# nixie_power.net
KiCad netlist of a schematic drawn in Altium Designer
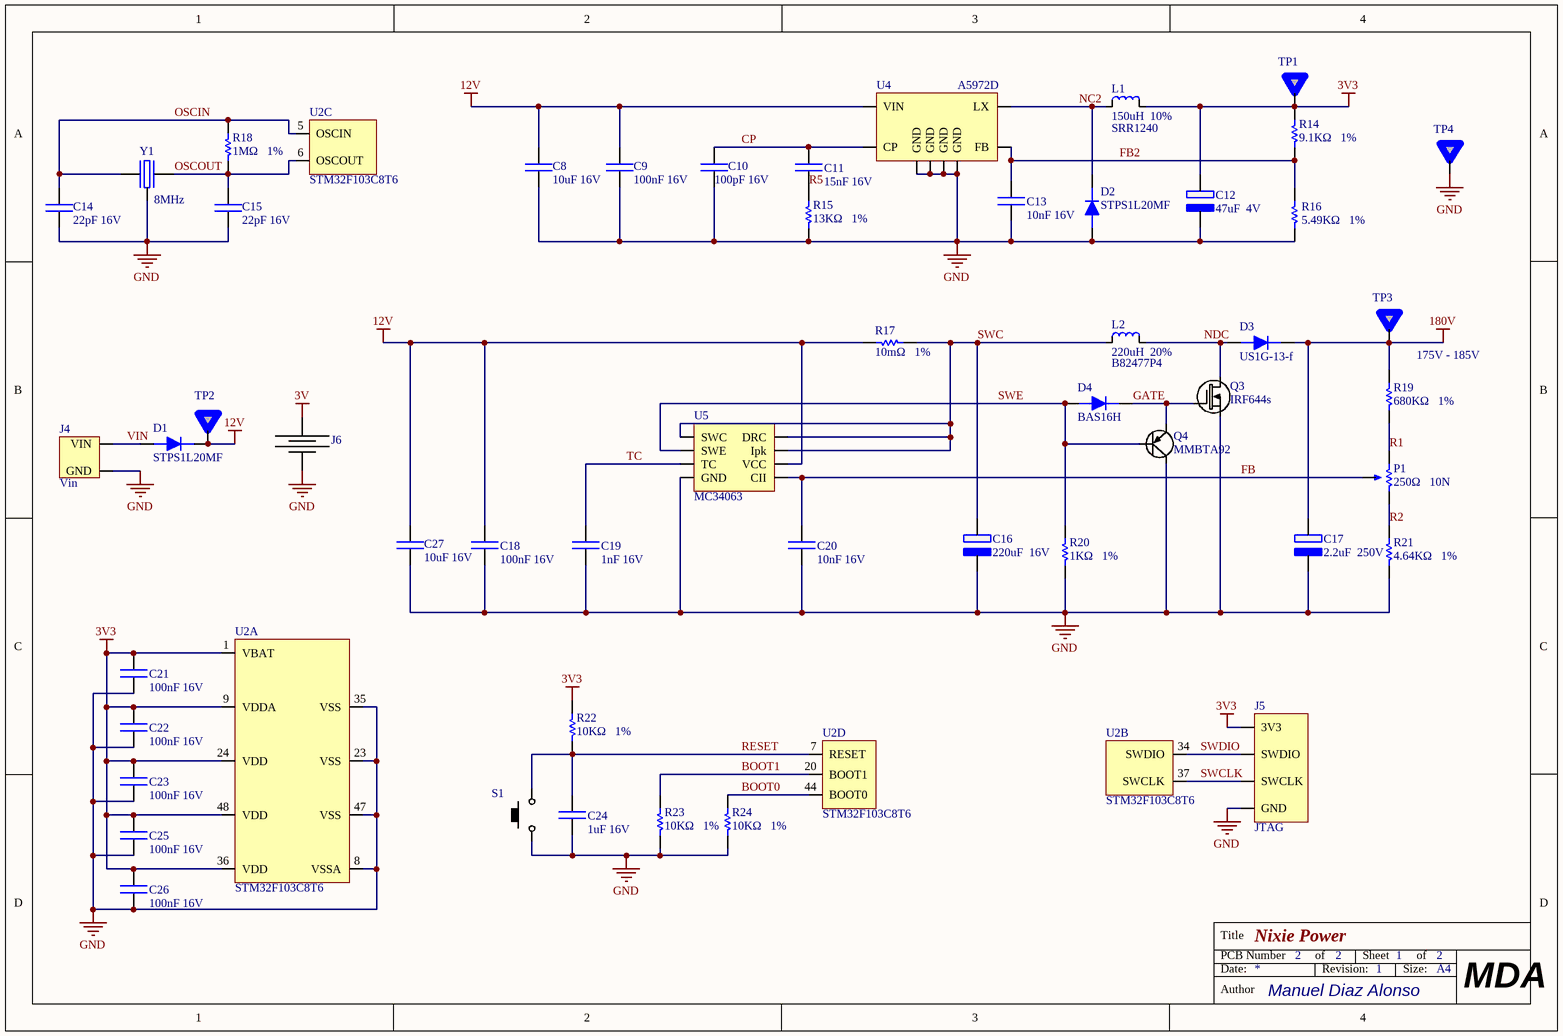
[diagram p0: nixie_power.SchDoc]

(export (version "E")
  (design (tool "Eeschema 10.0.6"))
  (components
    (comp (ref "C8") (value "10uF 16V") (footprint "0603") (libsource (lib "Nixielib") (part "CAP")))
    (comp (ref "C9") (value "100nF 16V") (footprint "0603") (libsource (lib "Nixielib") (part "CAP")))
    (comp (ref "C10") (value "100pF 16V") (footprint "0603") (libsource (lib "Nixielib") (part "CAP")))
    (comp (ref "C11") (value "15nF 16V") (footprint "0603") (libsource (lib "Nixielib") (part "CAP")))
    (comp (ref "C12")
      (value "47uF  4V")
      (footprint "AVX-B-CASE")
      (libsource (lib "Nixielib") (part "CAP_pol"))
    )
    (comp (ref "C13") (value "10nF 16V") (footprint "0603") (libsource (lib "Nixielib") (part "CAP")))
    (comp (ref "C14") (value "22pF 16V") (footprint "0603") (libsource (lib "Nixielib") (part "CAP")))
    (comp (ref "C15") (value "22pF 16V") (footprint "0603") (libsource (lib "Nixielib") (part "CAP")))
    (comp (ref "C16")
      (value "220uF  16V")
      (footprint "CAP-SIZE-F")
      (libsource (lib "Nixielib") (part "CAP_pol"))
    )
    (comp (ref "C17")
      (value "2.2uF  250V")
      (footprint "CAP-SIZE-F")
      (libsource (lib "Nixielib") (part "CAP_pol"))
    )
    (comp (ref "C18") (value "100nF 16V") (footprint "0603") (libsource (lib "Nixielib") (part "CAP")))
    (comp (ref "C19") (value "1nF 16V") (footprint "0603") (libsource (lib "Nixielib") (part "CAP")))
    (comp (ref "C20") (value "10nF 16V") (footprint "0603") (libsource (lib "Nixielib") (part "CAP")))
    (comp (ref "C21") (value "100nF 16V") (footprint "0603") (libsource (lib "Nixielib") (part "CAP")))
    (comp (ref "C22") (value "100nF 16V") (footprint "0603") (libsource (lib "Nixielib") (part "CAP")))
    (comp (ref "C23") (value "100nF 16V") (footprint "0603") (libsource (lib "Nixielib") (part "CAP")))
    (comp (ref "C24") (value "1uF 16V") (footprint "0603") (libsource (lib "Nixielib") (part "CAP")))
    (comp (ref "C25") (value "100nF 16V") (footprint "0603") (libsource (lib "Nixielib") (part "CAP")))
    (comp (ref "C26") (value "100nF 16V") (footprint "0603") (libsource (lib "Nixielib") (part "CAP")))
    (comp (ref "C27") (value "10uF 16V") (footprint "0603") (libsource (lib "Nixielib") (part "CAP")))
    (comp (ref "D1") (value "STPS1L20MF") (footprint "DO-222AA") (libsource (lib "MyLib") (part "DIO")))
    (comp (ref "D2") (value "STPS1L20MF") (footprint "DO-222AA") (libsource (lib "MyLib") (part "DIO")))
    (comp (ref "D3") (value "US1G-13-f") (footprint "SMA") (libsource (lib "MyLib") (part "DIO")))
    (comp (ref "D4") (value "BAS16H") (footprint "SOD-123F") (libsource (lib "MyLib") (part "DIO")))
    (comp (ref "J4")
      (value "Vin")
      (footprint "HEADERx2_POL")
      (description "282837-2")
      (libsource (lib "MyLib") (part "Vin"))
    )
    (comp (ref "J5")
      (value "JTAG")
      (footprint "PIN_1X4_HDR_RA")
      (description "TSW-104-08-F-S-RA")
      (libsource (lib "Nixielib") (part "JTAG"))
    )
    (comp (ref "J6")
      (value "BAT")
      (footprint "120591-1")
      (description "CR2032")
      (libsource (lib "MyLib") (part "BAT"))
    )
    (comp (ref "L1")
      (value "150uH  10%")
      (footprint "SRR1240")
      (description "SRR1240")
      (libsource (lib "MyLib") (part "IND"))
    )
    (comp (ref "L2")
      (value "220uH  20%")
      (footprint "12.5x12.5")
      (description "B82477P4")
      (libsource (lib "MyLib") (part "IND"))
    )
    (comp (ref "P1") (value "250Ω   10N") (footprint "3006P") (libsource (lib "Nixielib") (part "POTE")))
    (comp (ref "Q3") (value "IRF644s") (footprint "TO263-3S") (libsource (lib "Nixielib") (part "N-MOS")))
    (comp (ref "Q4") (value "MMBTA92") (footprint "SOT-23") (libsource (lib "Nixielib") (part "PNP")))
    (comp (ref "R14") (value "9.1KΩ   1%") (footprint "0603") (libsource (lib "Nixielib") (part "RES")))
    (comp (ref "R15") (value "13KΩ   1%") (footprint "0603") (libsource (lib "Nixielib") (part "RES")))
    (comp (ref "R16") (value "5.49KΩ   1%") (footprint "0603") (libsource (lib "Nixielib") (part "RES")))
    (comp (ref "R17") (value "10mΩ   1%") (footprint "0603") (libsource (lib "Nixielib") (part "RES")))
    (comp (ref "R18") (value "1MΩ   1%") (footprint "0603") (libsource (lib "Nixielib") (part "RES")))
    (comp (ref "R19") (value "680KΩ   1%") (footprint "0603") (libsource (lib "Nixielib") (part "RES")))
    (comp (ref "R20") (value "1KΩ   1%") (footprint "0603") (libsource (lib "Nixielib") (part "RES")))
    (comp (ref "R21") (value "4.64KΩ   1%") (footprint "0603") (libsource (lib "Nixielib") (part "RES")))
    (comp (ref "R22") (value "10KΩ   1%") (footprint "0603") (libsource (lib "Nixielib") (part "RES")))
    (comp (ref "R23") (value "10KΩ   1%") (footprint "0603") (libsource (lib "Nixielib") (part "RES")))
    (comp (ref "R24") (value "10KΩ   1%") (footprint "0603") (libsource (lib "Nixielib") (part "RES")))
    (comp (ref "S1") (value "RESET") (footprint "FSMSM") (libsource (lib "Nixielib") (part "BUTTON")))
    (comp (ref "TP1")
      (value "TEST-POINT")
      (footprint "Test_Point")
      (libsource (lib "Nixielib") (part "TEST-POINT"))
    )
    (comp (ref "TP2")
      (value "TEST-POINT")
      (footprint "Test_Point")
      (libsource (lib "Nixielib") (part "TEST-POINT"))
    )
    (comp (ref "TP3")
      (value "TEST-POINT")
      (footprint "Test_Point")
      (libsource (lib "Nixielib") (part "TEST-POINT"))
    )
    (comp (ref "TP4")
      (value "TEST-POINT")
      (footprint "Test_Point")
      (libsource (lib "Nixielib") (part "TEST-POINT"))
    )
    (comp (ref "U2")
      (value "STM32F103C8T6")
      (footprint "LQFP48")
      (libsource (lib "MyLib") (part "STM32F103C8T6"))
    )
    (comp (ref "U4") (value "A5972D") (footprint "SOIC-8") (libsource (lib "Nixielib") (part "A5972D")))
    (comp (ref "U5") (value "MC34063") (footprint "SOIC-8") (libsource (lib "Nixielib") (part "MC34063")))
    (comp (ref "Y1")
      (value "8MHz")
      (footprint "ABM3B")
      (description "ABM3B")
      (libsource (lib "Nixielib") (part "Cristal"))
    )
  )
  (nets
    (net (code "1") (name "/BOOT0") (class "Default")
      (node (ref "R24") (pin "2") (pinfunction "2_2") (pintype "passive"))
      (node (ref "U2") (pin "44") (pinfunction "BOOT0_44") (pintype "passive"))
    )
    (net (code "2") (name "/BOOT1") (class "Default")
      (node (ref "R23") (pin "2") (pinfunction "2_2") (pintype "passive"))
      (node (ref "U2") (pin "20") (pinfunction "BOOT1_20") (pintype "passive"))
    )
    (net (code "3") (name "/CP") (class "Default")
      (node (ref "C10") (pin "2") (pinfunction "2_2") (pintype "passive"))
      (node (ref "C11") (pin "2") (pinfunction "2_2") (pintype "passive"))
      (node (ref "U4") (pin "4") (pinfunction "CP_4") (pintype "passive"))
    )
    (net (code "4") (name "/FB") (class "Default")
      (node (ref "C20") (pin "2") (pinfunction "2_2") (pintype "passive"))
      (node (ref "P1") (pin "2") (pinfunction "2_2") (pintype "passive"))
      (node (ref "U5") (pin "5") (pinfunction "CII_5") (pintype "passive"))
    )
    (net (code "5") (name "/FB2") (class "Default")
      (node (ref "C13") (pin "2") (pinfunction "2_2") (pintype "passive"))
      (node (ref "R14") (pin "1") (pinfunction "1_1") (pintype "passive"))
      (node (ref "R16") (pin "1") (pinfunction "1_1") (pintype "passive"))
      (node (ref "U4") (pin "5") (pinfunction "FB_5") (pintype "passive"))
    )
    (net (code "6") (name "/GATE") (class "Default")
      (node (ref "D4") (pin "2") (pinfunction "2_2") (pintype "passive"))
      (node (ref "Q3") (pin "1") (pinfunction "G_1") (pintype "passive"))
      (node (ref "Q4") (pin "2") (pinfunction "E_2") (pintype "passive"))
    )
    (net (code "7") (name "/NC2") (class "Default")
      (node (ref "D2") (pin "2") (pinfunction "2_2") (pintype "passive"))
      (node (ref "L1") (pin "1") (pinfunction "1_1") (pintype "passive"))
      (node (ref "U4") (pin "1") (pinfunction "LX_1") (pintype "passive"))
    )
    (net (code "8") (name "/NDC") (class "Default")
      (node (ref "D3") (pin "1") (pinfunction "1_1") (pintype "passive"))
      (node (ref "L2") (pin "2") (pinfunction "2_2") (pintype "passive"))
      (node (ref "Q3") (pin "3") (pinfunction "D_3") (pintype "passive"))
    )
    (net (code "9") (name "/OSCIN") (class "Default")
      (node (ref "C14") (pin "2") (pinfunction "2_2") (pintype "passive"))
      (node (ref "R18") (pin "2") (pinfunction "2_2") (pintype "passive"))
      (node (ref "U2") (pin "5") (pinfunction "OSCIN_5") (pintype "passive"))
      (node (ref "Y1") (pin "1") (pinfunction "1_1") (pintype "passive"))
    )
    (net (code "10") (name "/OSCOUT") (class "Default")
      (node (ref "C15") (pin "2") (pinfunction "2_2") (pintype "passive"))
      (node (ref "R18") (pin "1") (pinfunction "1_1") (pintype "passive"))
      (node (ref "U2") (pin "6") (pinfunction "OSCOUT_6") (pintype "passive"))
      (node (ref "Y1") (pin "2") (pinfunction "2_2") (pintype "passive"))
    )
    (net (code "11") (name "/R1") (class "Default")
      (node (ref "P1") (pin "3") (pinfunction "3_3") (pintype "passive"))
      (node (ref "R19") (pin "1") (pinfunction "1_1") (pintype "passive"))
    )
    (net (code "12") (name "/R2") (class "Default")
      (node (ref "P1") (pin "1") (pinfunction "1_1") (pintype "passive"))
      (node (ref "R21") (pin "2") (pinfunction "2_2") (pintype "passive"))
    )
    (net (code "13") (name "/R5") (class "Default")
      (node (ref "C11") (pin "1") (pinfunction "1_1") (pintype "passive"))
      (node (ref "R15") (pin "2") (pinfunction "2_2") (pintype "passive"))
    )
    (net (code "14") (name "/RESET") (class "Default")
      (node (ref "C24") (pin "2") (pinfunction "2_2") (pintype "passive"))
      (node (ref "R22") (pin "1") (pinfunction "1_1") (pintype "passive"))
      (node (ref "S1") (pin "1") (pinfunction "1_1") (pintype "passive"))
      (node (ref "U2") (pin "7") (pinfunction "RESET_7") (pintype "passive"))
    )
    (net (code "15") (name "/SWC") (class "Default")
      (node (ref "C16") (pin "2") (pinfunction "2_2") (pintype "passive"))
      (node (ref "L2") (pin "1") (pinfunction "1_1") (pintype "passive"))
      (node (ref "R17") (pin "2") (pinfunction "2_2") (pintype "passive"))
      (node (ref "U5") (pin "1") (pinfunction "SWC_1") (pintype "passive"))
      (node (ref "U5") (pin "7") (pinfunction "Ipk_7") (pintype "passive"))
      (node (ref "U5") (pin "8") (pinfunction "DRC_8") (pintype "passive"))
    )
    (net (code "16") (name "/SWCLK") (class "Default")
      (node (ref "J5") (pin "3") (pinfunction "SWCLK_3") (pintype "passive"))
      (node (ref "U2") (pin "37") (pinfunction "SWCLK_37") (pintype "passive"))
    )
    (net (code "17") (name "/SWDIO") (class "Default")
      (node (ref "J5") (pin "2") (pinfunction "SWDIO_2") (pintype "passive"))
      (node (ref "U2") (pin "34") (pinfunction "SWDIO_34") (pintype "passive"))
    )
    (net (code "18") (name "/SWE") (class "Default")
      (node (ref "D4") (pin "1") (pinfunction "1_1") (pintype "passive"))
      (node (ref "Q4") (pin "1") (pinfunction "B_1") (pintype "passive"))
      (node (ref "R20") (pin "2") (pinfunction "2_2") (pintype "passive"))
      (node (ref "U5") (pin "2") (pinfunction "SWE_2") (pintype "passive"))
    )
    (net (code "19") (name "/TC") (class "Default")
      (node (ref "C19") (pin "2") (pinfunction "2_2") (pintype "passive"))
      (node (ref "U5") (pin "3") (pinfunction "TC_3") (pintype "passive"))
    )
    (net (code "20") (name "/VIN") (class "Default")
      (node (ref "D1") (pin "1") (pinfunction "1_1") (pintype "passive"))
      (node (ref "J4") (pin "1") (pinfunction "VIN_1") (pintype "passive"))
    )
    (net (code "21") (name "3V") (class "Default")
      (node (ref "J6") (pin "1") (pinfunction "+_1") (pintype "passive"))
    )
    (net (code "22") (name "3V3") (class "Default")
      (node (ref "C12") (pin "2") (pinfunction "2_2") (pintype "passive"))
      (node (ref "C21") (pin "1") (pinfunction "1_1") (pintype "passive"))
      (node (ref "C22") (pin "1") (pinfunction "1_1") (pintype "passive"))
      (node (ref "C23") (pin "1") (pinfunction "1_1") (pintype "passive"))
      (node (ref "C25") (pin "1") (pinfunction "1_1") (pintype "passive"))
      (node (ref "C26") (pin "1") (pinfunction "1_1") (pintype "passive"))
      (node (ref "J5") (pin "1") (pinfunction "3V3_1") (pintype "passive"))
      (node (ref "L1") (pin "2") (pinfunction "2_2") (pintype "passive"))
      (node (ref "R14") (pin "2") (pinfunction "2_2") (pintype "passive"))
      (node (ref "R22") (pin "2") (pinfunction "2_2") (pintype "passive"))
      (node (ref "TP1") (pin "1") (pinfunction "1_1") (pintype "passive"))
      (node (ref "U2") (pin "1") (pinfunction "VBAT_1") (pintype "passive"))
      (node (ref "U2") (pin "24") (pinfunction "VDD_24") (pintype "passive"))
      (node (ref "U2") (pin "36") (pinfunction "VDD_36") (pintype "passive"))
      (node (ref "U2") (pin "48") (pinfunction "VDD_48") (pintype "passive"))
      (node (ref "U2") (pin "9") (pinfunction "VDDA_9") (pintype "passive"))
    )
    (net (code "23") (name "12V") (class "Default")
      (node (ref "C18") (pin "2") (pinfunction "2_2") (pintype "passive"))
      (node (ref "C27") (pin "2") (pinfunction "2_2") (pintype "passive"))
      (node (ref "C8") (pin "2") (pinfunction "2_2") (pintype "passive"))
      (node (ref "C9") (pin "2") (pinfunction "2_2") (pintype "passive"))
      (node (ref "D1") (pin "2") (pinfunction "2_2") (pintype "passive"))
      (node (ref "R17") (pin "1") (pinfunction "1_1") (pintype "passive"))
      (node (ref "TP2") (pin "1") (pinfunction "1_1") (pintype "passive"))
      (node (ref "U4") (pin "8") (pinfunction "VIN_8") (pintype "passive"))
      (node (ref "U5") (pin "6") (pinfunction "VCC_6") (pintype "passive"))
    )
    (net (code "24") (name "180V") (class "Default")
      (node (ref "C17") (pin "2") (pinfunction "2_2") (pintype "passive"))
      (node (ref "D3") (pin "2") (pinfunction "2_2") (pintype "passive"))
      (node (ref "R19") (pin "2") (pinfunction "2_2") (pintype "passive"))
      (node (ref "TP3") (pin "1") (pinfunction "1_1") (pintype "passive"))
    )
    (net (code "25") (name "GND") (class "Default")
      (node (ref "C10") (pin "1") (pinfunction "1_1") (pintype "passive"))
      (node (ref "C12") (pin "1") (pinfunction "1_1") (pintype "passive"))
      (node (ref "C13") (pin "1") (pinfunction "1_1") (pintype "passive"))
      (node (ref "C14") (pin "1") (pinfunction "1_1") (pintype "passive"))
      (node (ref "C15") (pin "1") (pinfunction "1_1") (pintype "passive"))
      (node (ref "C16") (pin "1") (pinfunction "1_1") (pintype "passive"))
      (node (ref "C17") (pin "1") (pinfunction "1_1") (pintype "passive"))
      (node (ref "C18") (pin "1") (pinfunction "1_1") (pintype "passive"))
      (node (ref "C19") (pin "1") (pinfunction "1_1") (pintype "passive"))
      (node (ref "C20") (pin "1") (pinfunction "1_1") (pintype "passive"))
      (node (ref "C21") (pin "2") (pinfunction "2_2") (pintype "passive"))
      (node (ref "C22") (pin "2") (pinfunction "2_2") (pintype "passive"))
      (node (ref "C23") (pin "2") (pinfunction "2_2") (pintype "passive"))
      (node (ref "C24") (pin "1") (pinfunction "1_1") (pintype "passive"))
      (node (ref "C25") (pin "2") (pinfunction "2_2") (pintype "passive"))
      (node (ref "C26") (pin "2") (pinfunction "2_2") (pintype "passive"))
      (node (ref "C27") (pin "1") (pinfunction "1_1") (pintype "passive"))
      (node (ref "C8") (pin "1") (pinfunction "1_1") (pintype "passive"))
      (node (ref "C9") (pin "1") (pinfunction "1_1") (pintype "passive"))
      (node (ref "D2") (pin "1") (pinfunction "1_1") (pintype "passive"))
      (node (ref "J4") (pin "2") (pinfunction "GND_2") (pintype "passive"))
      (node (ref "J5") (pin "4") (pinfunction "GND_4") (pintype "passive"))
      (node (ref "J6") (pin "2") (pinfunction "-_2") (pintype "passive"))
      (node (ref "Q3") (pin "2") (pinfunction "S_2") (pintype "passive"))
      (node (ref "Q4") (pin "3") (pinfunction "C_3") (pintype "passive"))
      (node (ref "R15") (pin "1") (pinfunction "1_1") (pintype "passive"))
      (node (ref "R16") (pin "2") (pinfunction "2_2") (pintype "passive"))
      (node (ref "R20") (pin "1") (pinfunction "1_1") (pintype "passive"))
      (node (ref "R21") (pin "1") (pinfunction "1_1") (pintype "passive"))
      (node (ref "R23") (pin "1") (pinfunction "1_1") (pintype "passive"))
      (node (ref "R24") (pin "1") (pinfunction "1_1") (pintype "passive"))
      (node (ref "S1") (pin "2") (pinfunction "2_2") (pintype "passive"))
      (node (ref "TP4") (pin "1") (pinfunction "1_1") (pintype "passive"))
      (node (ref "U2") (pin "23") (pinfunction "VSS_23") (pintype "passive"))
      (node (ref "U2") (pin "35") (pinfunction "VSS_35") (pintype "passive"))
      (node (ref "U2") (pin "47") (pinfunction "VSS_47") (pintype "passive"))
      (node (ref "U2") (pin "8") (pinfunction "VSSA_8") (pintype "passive"))
      (node (ref "U4") (pin "2") (pinfunction "GND_2") (pintype "passive"))
      (node (ref "U4") (pin "3") (pinfunction "GND_3") (pintype "passive"))
      (node (ref "U4") (pin "6") (pinfunction "GND_6") (pintype "passive"))
      (node (ref "U4") (pin "7") (pinfunction "GND_7") (pintype "passive"))
      (node (ref "U5") (pin "4") (pinfunction "GND_4") (pintype "passive"))
      (node (ref "Y1") (pin "3") (pinfunction "3_3") (pintype "passive"))
    )
  )
)
